# -20_to_-12.net
KiCad netlist of a schematic drawn in Altium Designer
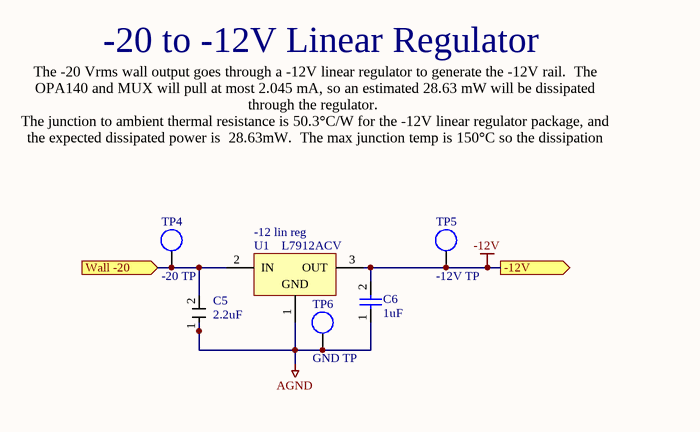
[diagram p0: -20_to_-12.SchDoc]

(export (version "E")
  (design (tool "Eeschema 10.0.6"))
  (components
    (comp (ref "C5")
      (value "2.2uF")
      (footprint "CAPMP3216X180N")
      (libsource (lib "California Institute of Technology") (part "F931V225KAA-Symbol-1"))
    )
    (comp (ref "C6")
      (value "1uF")
      (footprint "CAPC2113X120X50LL20T30")
      (fields
        (field (name "MANUFACTURER") "AVX Interconnect / Elco")
        (field (name "PART NUMBER") "TAJR105K020RNJ")
      )
      (libsource (lib "Altium Content Vault") (part "CAP"))
    )
    (comp (ref "TP4")
      (value "-20 TP")
      (footprint "PCBComponent_1")
      (libsource (lib "test-point") (part "Component_1"))
    )
    (comp (ref "TP5")
      (value "-12V TP")
      (footprint "PCBComponent_1")
      (libsource (lib "test-point") (part "Component_1"))
    )
    (comp (ref "TP6")
      (value "GND TP")
      (footprint "PCBComponent_1")
      (libsource (lib "test-point") (part "Component_1"))
    )
    (comp (ref "U1")
      (value "L7912ACV")
      (footprint "TO220")
      (description "2% Negative Voltage Regulator, -12V, 3-Pin TO-220")
      (libsource (lib "Altium Content Vault") (part "PM-REG-7905-SIL3"))
    )
  )
  (nets
    (net (code "1") (name "-12V") (class "Default")
      (node (ref "C6") (pin "2") (pinfunction "2_2") (pintype "passive"))
      (node (ref "TP5") (pin "TP") (pinfunction "TP_TP") (pintype "passive"))
      (node (ref "U1") (pin "3") (pinfunction "OUT_3") (pintype "power_in"))
    )
    (net (code "2") (name "/Wall -20") (class "Default")
      (node (ref "C5") (pin "2") (pinfunction "-_2") (pintype "passive"))
      (node (ref "TP4") (pin "TP") (pinfunction "TP_TP") (pintype "passive"))
      (node (ref "U1") (pin "2") (pinfunction "IN_2") (pintype "power_in"))
    )
    (net (code "3") (name "AGND") (class "Default")
      (node (ref "C5") (pin "1") (pinfunction "-_1") (pintype "passive"))
      (node (ref "C6") (pin "1") (pinfunction "1_1") (pintype "passive"))
      (node (ref "TP6") (pin "TP") (pinfunction "TP_TP") (pintype "passive"))
      (node (ref "U1") (pin "1") (pinfunction "GND_1") (pintype "power_in"))
    )
  )
)
